# iso_GPIO_4in_4out.net
KiCad netlist of a schematic drawn in Altium Designer
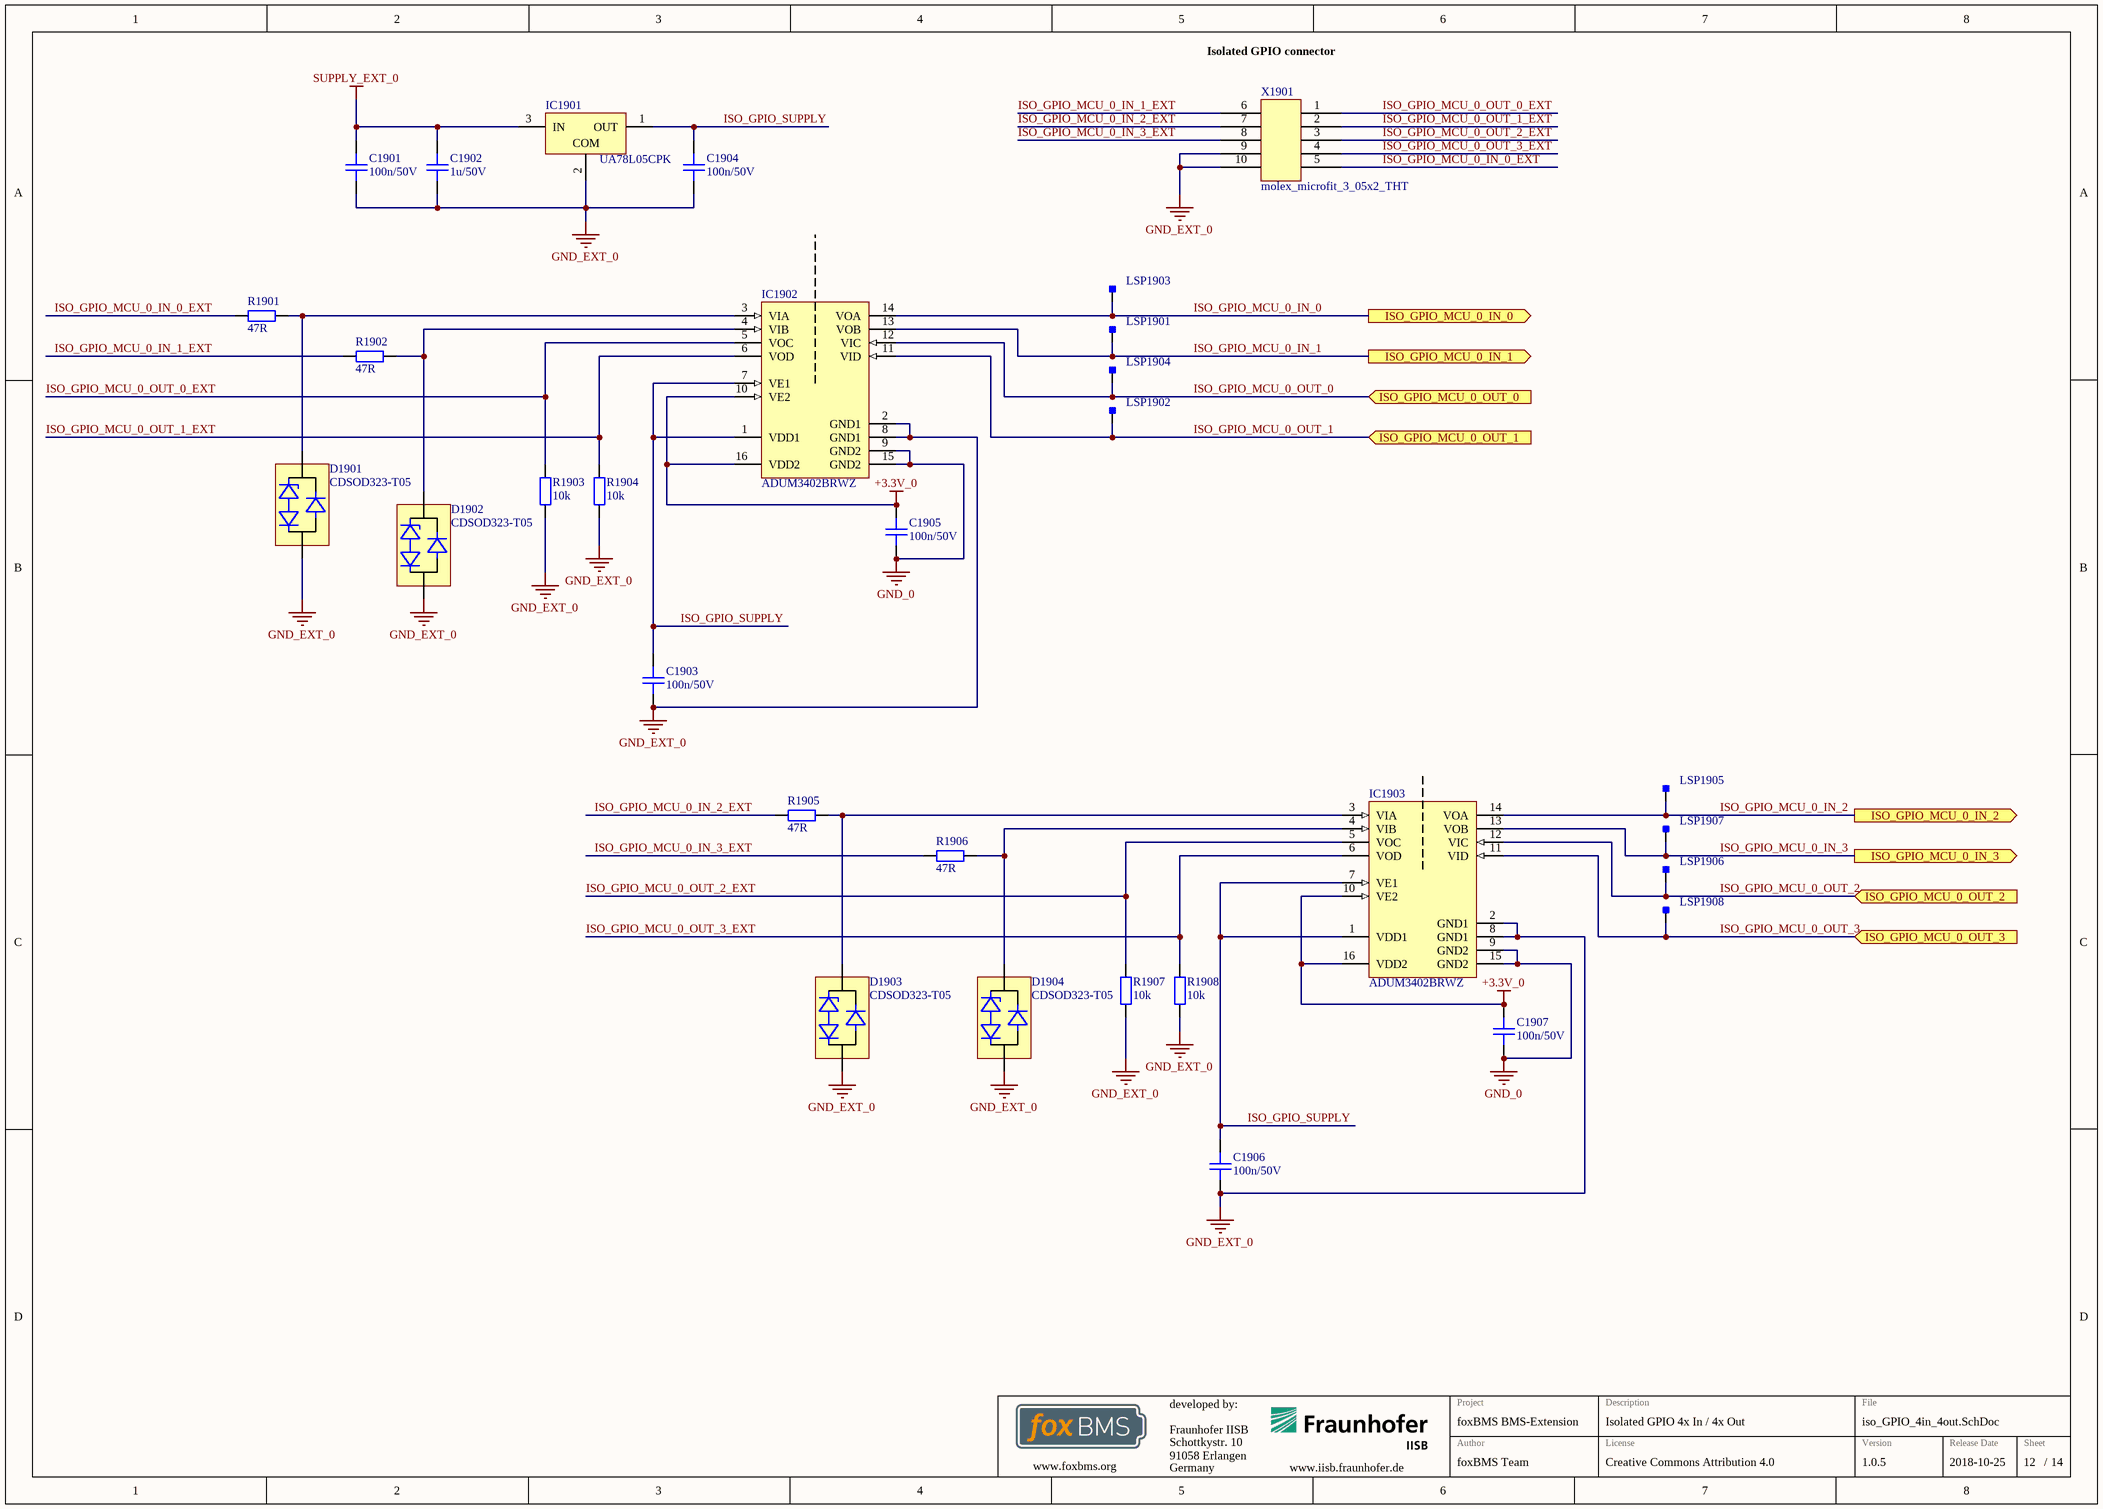
[diagram p0: iso_GPIO_4in_4out.SchDoc]

(export (version "E")
  (design (tool "Eeschema 10.0.6"))
  (components
    (comp (ref "C1901")
      (value "100n/50V")
      (footprint "CAPC1608X08N")
      (description "MLCC")
      (fields (field (name "PART NUMBER") "gen_C_ceramic_100n_50V_X7R_0603"))
      (libsource (lib "OE750") (part "C"))
    )
    (comp (ref "C1902")
      (value "1u/50V")
      (footprint "CAPC1608X08N")
      (description "MLCC")
      (fields (field (name "PART NUMBER") "gen_C_ceramic_1u_50V_X7R_0603") (field (name "TOLERANCE") "± 10%"))
      (libsource (lib "OE750") (part "C"))
    )
    (comp (ref "C1903")
      (value "100n/50V")
      (footprint "CAPC1608X08N")
      (description "MLCC")
      (fields (field (name "PART NUMBER") "gen_C_ceramic_100n_50V_X7R_0603"))
      (libsource (lib "OE750") (part "C"))
    )
    (comp (ref "C1904")
      (value "100n/50V")
      (footprint "CAPC1608X08N")
      (description "MLCC")
      (fields (field (name "PART NUMBER") "gen_C_ceramic_100n_50V_X7R_0603"))
      (libsource (lib "OE750") (part "C"))
    )
    (comp (ref "C1905")
      (value "100n/50V")
      (footprint "CAPC1608X08N")
      (description "MLCC")
      (fields (field (name "PART NUMBER") "gen_C_ceramic_100n_50V_X7R_0603"))
      (libsource (lib "OE750") (part "C"))
    )
    (comp (ref "C1906")
      (value "100n/50V")
      (footprint "CAPC1608X08N")
      (description "MLCC")
      (fields (field (name "PART NUMBER") "gen_C_ceramic_100n_50V_X7R_0603"))
      (libsource (lib "OE750") (part "C"))
    )
    (comp (ref "C1907")
      (value "100n/50V")
      (footprint "CAPC1608X08N")
      (description "MLCC")
      (fields (field (name "PART NUMBER") "gen_C_ceramic_100n_50V_X7R_0603"))
      (libsource (lib "OE750") (part "C"))
    )
    (comp (ref "D1901")
      (value "CDSOD323-T05")
      (footprint "SODFL250X110-2N")
      (description "TVS Diode, CDSOD323 Series, Unidirectional, 5 V, 18.3 V, SOD-323, 2 Pins")
      (fields (field (name "MANUFACTURER") "Bourns"))
      (libsource (lib "OE750") (part "D_TVS_uni"))
    )
    (comp (ref "D1902")
      (value "CDSOD323-T05")
      (footprint "SODFL250X110-2N")
      (description "TVS Diode, CDSOD323 Series, Unidirectional, 5 V, 18.3 V, SOD-323, 2 Pins")
      (fields (field (name "MANUFACTURER") "Bourns"))
      (libsource (lib "OE750") (part "D_TVS_uni"))
    )
    (comp (ref "D1903")
      (value "CDSOD323-T05")
      (footprint "SODFL250X110-2N")
      (description "TVS Diode, CDSOD323 Series, Unidirectional, 5 V, 18.3 V, SOD-323, 2 Pins")
      (fields (field (name "MANUFACTURER") "Bourns"))
      (libsource (lib "OE750") (part "D_TVS_uni"))
    )
    (comp (ref "D1904")
      (value "CDSOD323-T05")
      (footprint "SODFL250X110-2N")
      (description "TVS Diode, CDSOD323 Series, Unidirectional, 5 V, 18.3 V, SOD-323, 2 Pins")
      (fields (field (name "MANUFACTURER") "Bourns"))
      (libsource (lib "OE750") (part "D_TVS_uni"))
    )
    (comp (ref "IC1901")
      (value "UA78L05CPK")
      (footprint "PK0003A_L")
      (fields (field (name "MANUFACTURER") "TexasInstruments"))
      (libsource (lib "Altium Content Vault") (part "TI-UA78L05-PK-3"))
    )
    (comp (ref "IC1902")
      (value "ADUM3402BRWZ")
      (footprint "ADI-RW-16_N")
      (fields (field (name "MANUFACTURER") "Analog Devices"))
      (libsource (lib "Altium Content Vault") (part "ADI-ADUMXXX2-XX-16"))
    )
    (comp (ref "IC1903")
      (value "ADUM3402BRWZ")
      (footprint "ADI-RW-16_N")
      (fields (field (name "MANUFACTURER") "Analog Devices"))
      (libsource (lib "Altium Content Vault") (part "ADI-ADUMXXX2-XX-16"))
    )
    (comp (ref "LSP1901")
      (value "Testpoint_Square")
      (footprint "Testpoint_S1")
      (description "Testpoint, square")
      (libsource (lib "OE750") (part "Testpoint_Square"))
    )
    (comp (ref "LSP1902")
      (value "Testpoint_Square")
      (footprint "Testpoint_S1")
      (description "Testpoint, square")
      (libsource (lib "OE750") (part "Testpoint_Square"))
    )
    (comp (ref "LSP1903")
      (value "Testpoint_Square")
      (footprint "Testpoint_S1")
      (description "Testpoint, square")
      (libsource (lib "OE750") (part "Testpoint_Square"))
    )
    (comp (ref "LSP1904")
      (value "Testpoint_Square")
      (footprint "Testpoint_S1")
      (description "Testpoint, square")
      (libsource (lib "OE750") (part "Testpoint_Square"))
    )
    (comp (ref "LSP1905")
      (value "Testpoint_Square")
      (footprint "Testpoint_S1")
      (description "Testpoint, square")
      (libsource (lib "OE750") (part "Testpoint_Square"))
    )
    (comp (ref "LSP1906")
      (value "Testpoint_Square")
      (footprint "Testpoint_S1")
      (description "Testpoint, square")
      (libsource (lib "OE750") (part "Testpoint_Square"))
    )
    (comp (ref "LSP1907")
      (value "Testpoint_Square")
      (footprint "Testpoint_S1")
      (description "Testpoint, square")
      (libsource (lib "OE750") (part "Testpoint_Square"))
    )
    (comp (ref "LSP1908")
      (value "Testpoint_Square")
      (footprint "Testpoint_S1")
      (description "Testpoint, square")
      (libsource (lib "OE750") (part "Testpoint_Square"))
    )
    (comp (ref "R1901")
      (value "47R")
      (footprint "RESC1608X05N")
      (description "SMD Resistor 47R 0603")
      (fields (field (name "PART NUMBER") "gen_R_47R_0603") (field (name "TOLERANCE") "1%"))
      (libsource (lib "OE750") (part "R"))
    )
    (comp (ref "R1902")
      (value "47R")
      (footprint "RESC1608X05N")
      (description "SMD Resistor 47R 0603")
      (fields (field (name "PART NUMBER") "gen_R_47R_0603") (field (name "TOLERANCE") "1%"))
      (libsource (lib "OE750") (part "R"))
    )
    (comp (ref "R1903")
      (value "10k")
      (footprint "RESC1608X05N")
      (description "SMD Resistor 10k 0603")
      (fields (field (name "PART NUMBER") "gen_R_10k_0603") (field (name "TOLERANCE") "1%"))
      (libsource (lib "OE750") (part "R"))
    )
    (comp (ref "R1904")
      (value "10k")
      (footprint "RESC1608X05N")
      (description "SMD Resistor 10k 0603")
      (fields (field (name "PART NUMBER") "gen_R_10k_0603") (field (name "TOLERANCE") "1%"))
      (libsource (lib "OE750") (part "R"))
    )
    (comp (ref "R1905")
      (value "47R")
      (footprint "RESC1608X05N")
      (description "SMD Resistor 47R 0603")
      (fields (field (name "PART NUMBER") "gen_R_47R_0603") (field (name "TOLERANCE") "1%"))
      (libsource (lib "OE750") (part "R"))
    )
    (comp (ref "R1906")
      (value "47R")
      (footprint "RESC1608X05N")
      (description "SMD Resistor 47R 0603")
      (fields (field (name "PART NUMBER") "gen_R_47R_0603") (field (name "TOLERANCE") "1%"))
      (libsource (lib "OE750") (part "R"))
    )
    (comp (ref "R1907")
      (value "10k")
      (footprint "RESC1608X05N")
      (description "SMD Resistor 10k 0603")
      (fields (field (name "PART NUMBER") "gen_R_10k_0603") (field (name "TOLERANCE") "1%"))
      (libsource (lib "OE750") (part "R"))
    )
    (comp (ref "R1908")
      (value "10k")
      (footprint "RESC1608X05N")
      (description "SMD Resistor 10k 0603")
      (fields (field (name "PART NUMBER") "gen_R_10k_0603") (field (name "TOLERANCE") "1%"))
      (libsource (lib "OE750") (part "R"))
    )
    (comp (ref "X1901")
      (value "molex_microfit_3_05x2_THT")
      (footprint "MOLEX_MICROFIT_05x2_THT")
      (fields (field (name "MANUFACTURER") "Molex"))
      (libsource (lib "OE750") (part "X5x2"))
    )
  )
  (nets
    (net (code "1") (name "+3.3V_0") (class "Default")
      (node (ref "C1905") (pin "1") (pinfunction "1_1") (pintype "passive"))
      (node (ref "C1907") (pin "1") (pinfunction "1_1") (pintype "passive"))
      (node (ref "IC1902") (pin "10") (pinfunction "VE2_10") (pintype "input"))
      (node (ref "IC1902") (pin "16") (pinfunction "VDD2_16") (pintype "power_in"))
      (node (ref "IC1903") (pin "10") (pinfunction "VE2_10") (pintype "input"))
      (node (ref "IC1903") (pin "16") (pinfunction "VDD2_16") (pintype "power_in"))
    )
    (net (code "2") (name "/ISO_GPIO_MCU_0_IN_0") (class "Default")
      (node (ref "IC1902") (pin "14") (pinfunction "VOA_14") (pintype "tri_state"))
      (node (ref "LSP1903") (pin "1") (pinfunction "1_1") (pintype "passive"))
    )
    (net (code "3") (name "/ISO_GPIO_MCU_0_IN_0_EXT") (class "Default")
      (node (ref "R1901") (pin "2") (pinfunction "2_2") (pintype "passive"))
      (node (ref "X1901") (pin "5") (pintype "passive"))
    )
    (net (code "4") (name "/ISO_GPIO_MCU_0_IN_1") (class "Default")
      (node (ref "IC1902") (pin "13") (pinfunction "VOB_13") (pintype "tri_state"))
      (node (ref "LSP1901") (pin "1") (pinfunction "1_1") (pintype "passive"))
    )
    (net (code "5") (name "/ISO_GPIO_MCU_0_IN_1_EXT") (class "Default")
      (node (ref "R1902") (pin "2") (pinfunction "2_2") (pintype "passive"))
      (node (ref "X1901") (pin "6") (pintype "passive"))
    )
    (net (code "6") (name "/ISO_GPIO_MCU_0_IN_2") (class "Default")
      (node (ref "IC1903") (pin "14") (pinfunction "VOA_14") (pintype "tri_state"))
      (node (ref "LSP1905") (pin "1") (pinfunction "1_1") (pintype "passive"))
    )
    (net (code "7") (name "/ISO_GPIO_MCU_0_IN_2_EXT") (class "Default")
      (node (ref "R1905") (pin "2") (pinfunction "2_2") (pintype "passive"))
      (node (ref "X1901") (pin "7") (pintype "passive"))
    )
    (net (code "8") (name "/ISO_GPIO_MCU_0_IN_3") (class "Default")
      (node (ref "IC1903") (pin "13") (pinfunction "VOB_13") (pintype "tri_state"))
      (node (ref "LSP1907") (pin "1") (pinfunction "1_1") (pintype "passive"))
    )
    (net (code "9") (name "/ISO_GPIO_MCU_0_IN_3_EXT") (class "Default")
      (node (ref "R1906") (pin "2") (pinfunction "2_2") (pintype "passive"))
      (node (ref "X1901") (pin "8") (pintype "passive"))
    )
    (net (code "10") (name "/ISO_GPIO_MCU_0_OUT_0") (class "Default")
      (node (ref "IC1902") (pin "12") (pinfunction "VIC_12") (pintype "input"))
      (node (ref "LSP1904") (pin "1") (pinfunction "1_1") (pintype "passive"))
    )
    (net (code "11") (name "/ISO_GPIO_MCU_0_OUT_0_EXT") (class "Default")
      (node (ref "IC1902") (pin "5") (pinfunction "VOC_5") (pintype "tri_state"))
      (node (ref "R1903") (pin "2") (pinfunction "2_2") (pintype "passive"))
      (node (ref "X1901") (pin "1") (pintype "passive"))
    )
    (net (code "12") (name "/ISO_GPIO_MCU_0_OUT_1") (class "Default")
      (node (ref "IC1902") (pin "11") (pinfunction "VID_11") (pintype "input"))
      (node (ref "LSP1902") (pin "1") (pinfunction "1_1") (pintype "passive"))
    )
    (net (code "13") (name "/ISO_GPIO_MCU_0_OUT_1_EXT") (class "Default")
      (node (ref "IC1902") (pin "6") (pinfunction "VOD_6") (pintype "tri_state"))
      (node (ref "R1904") (pin "2") (pinfunction "2_2") (pintype "passive"))
      (node (ref "X1901") (pin "2") (pintype "passive"))
    )
    (net (code "14") (name "/ISO_GPIO_MCU_0_OUT_2") (class "Default")
      (node (ref "IC1903") (pin "12") (pinfunction "VIC_12") (pintype "input"))
      (node (ref "LSP1906") (pin "1") (pinfunction "1_1") (pintype "passive"))
    )
    (net (code "15") (name "/ISO_GPIO_MCU_0_OUT_2_EXT") (class "Default")
      (node (ref "IC1903") (pin "5") (pinfunction "VOC_5") (pintype "tri_state"))
      (node (ref "R1907") (pin "2") (pinfunction "2_2") (pintype "passive"))
      (node (ref "X1901") (pin "3") (pintype "passive"))
    )
    (net (code "16") (name "/ISO_GPIO_MCU_0_OUT_3") (class "Default")
      (node (ref "IC1903") (pin "11") (pinfunction "VID_11") (pintype "input"))
      (node (ref "LSP1908") (pin "1") (pinfunction "1_1") (pintype "passive"))
    )
    (net (code "17") (name "/ISO_GPIO_MCU_0_OUT_3_EXT") (class "Default")
      (node (ref "IC1903") (pin "6") (pinfunction "VOD_6") (pintype "tri_state"))
      (node (ref "R1908") (pin "2") (pinfunction "2_2") (pintype "passive"))
      (node (ref "X1901") (pin "4") (pintype "passive"))
    )
    (net (code "18") (name "/ISO_GPIO_SUPPLY") (class "Default")
      (node (ref "C1903") (pin "1") (pinfunction "1_1") (pintype "passive"))
      (node (ref "C1904") (pin "1") (pinfunction "1_1") (pintype "passive"))
      (node (ref "C1906") (pin "1") (pinfunction "1_1") (pintype "passive"))
      (node (ref "IC1901") (pin "1") (pinfunction "OUT_1") (pintype "power_in"))
      (node (ref "IC1902") (pin "1") (pinfunction "VDD1_1") (pintype "power_in"))
      (node (ref "IC1902") (pin "7") (pinfunction "VE1_7") (pintype "input"))
      (node (ref "IC1903") (pin "1") (pinfunction "VDD1_1") (pintype "power_in"))
      (node (ref "IC1903") (pin "7") (pinfunction "VE1_7") (pintype "input"))
    )
    (net (code "19") (name "GND_0") (class "Default")
      (node (ref "C1905") (pin "2") (pinfunction "2_2") (pintype "passive"))
      (node (ref "C1907") (pin "2") (pinfunction "2_2") (pintype "passive"))
      (node (ref "IC1902") (pin "15") (pinfunction "GND2_15") (pintype "power_in"))
      (node (ref "IC1902") (pin "9") (pinfunction "GND2_9") (pintype "power_in"))
      (node (ref "IC1903") (pin "15") (pinfunction "GND2_15") (pintype "power_in"))
      (node (ref "IC1903") (pin "9") (pinfunction "GND2_9") (pintype "power_in"))
    )
    (net (code "20") (name "GND_EXT_0") (class "Default")
      (node (ref "C1901") (pin "2") (pinfunction "2_2") (pintype "passive"))
      (node (ref "C1902") (pin "2") (pinfunction "2_2") (pintype "passive"))
      (node (ref "C1903") (pin "2") (pinfunction "2_2") (pintype "passive"))
      (node (ref "C1904") (pin "2") (pinfunction "2_2") (pintype "passive"))
      (node (ref "C1906") (pin "2") (pinfunction "2_2") (pintype "passive"))
      (node (ref "D1901") (pin "2") (pinfunction "A_2") (pintype "passive"))
      (node (ref "D1902") (pin "2") (pinfunction "A_2") (pintype "passive"))
      (node (ref "D1903") (pin "2") (pinfunction "A_2") (pintype "passive"))
      (node (ref "D1904") (pin "2") (pinfunction "A_2") (pintype "passive"))
      (node (ref "IC1901") (pin "2") (pinfunction "COM_2") (pintype "power_in"))
      (node (ref "IC1902") (pin "2") (pinfunction "GND1_2") (pintype "power_in"))
      (node (ref "IC1902") (pin "8") (pinfunction "GND1_8") (pintype "power_in"))
      (node (ref "IC1903") (pin "2") (pinfunction "GND1_2") (pintype "power_in"))
      (node (ref "IC1903") (pin "8") (pinfunction "GND1_8") (pintype "power_in"))
      (node (ref "R1903") (pin "1") (pinfunction "1_1") (pintype "passive"))
      (node (ref "R1904") (pin "1") (pinfunction "1_1") (pintype "passive"))
      (node (ref "R1907") (pin "1") (pinfunction "1_1") (pintype "passive"))
      (node (ref "R1908") (pin "1") (pinfunction "1_1") (pintype "passive"))
      (node (ref "X1901") (pin "10") (pintype "passive"))
      (node (ref "X1901") (pin "9") (pintype "passive"))
    )
    (net (code "21") (name "Net-(D1901-K)") (class "Default")
      (node (ref "D1901") (pin "1") (pinfunction "K_1") (pintype "passive"))
      (node (ref "IC1902") (pin "3") (pinfunction "VIA_3") (pintype "input"))
      (node (ref "R1901") (pin "1") (pinfunction "1_1") (pintype "passive"))
    )
    (net (code "22") (name "Net-(D1902-K)") (class "Default")
      (node (ref "D1902") (pin "1") (pinfunction "K_1") (pintype "passive"))
      (node (ref "IC1902") (pin "4") (pinfunction "VIB_4") (pintype "input"))
      (node (ref "R1902") (pin "1") (pinfunction "1_1") (pintype "passive"))
    )
    (net (code "23") (name "Net-(D1903-K)") (class "Default")
      (node (ref "D1903") (pin "1") (pinfunction "K_1") (pintype "passive"))
      (node (ref "IC1903") (pin "3") (pinfunction "VIA_3") (pintype "input"))
      (node (ref "R1905") (pin "1") (pinfunction "1_1") (pintype "passive"))
    )
    (net (code "24") (name "Net-(D1904-K)") (class "Default")
      (node (ref "D1904") (pin "1") (pinfunction "K_1") (pintype "passive"))
      (node (ref "IC1903") (pin "4") (pinfunction "VIB_4") (pintype "input"))
      (node (ref "R1906") (pin "1") (pinfunction "1_1") (pintype "passive"))
    )
    (net (code "25") (name "SUPPLY_EXT_0") (class "Default")
      (node (ref "C1901") (pin "1") (pinfunction "1_1") (pintype "passive"))
      (node (ref "C1902") (pin "1") (pinfunction "1_1") (pintype "passive"))
      (node (ref "IC1901") (pin "3") (pinfunction "IN_3") (pintype "power_in"))
    )
  )
)
